# RS485_Communication_Layer.net
KiCad netlist of a schematic drawn in Altium Designer
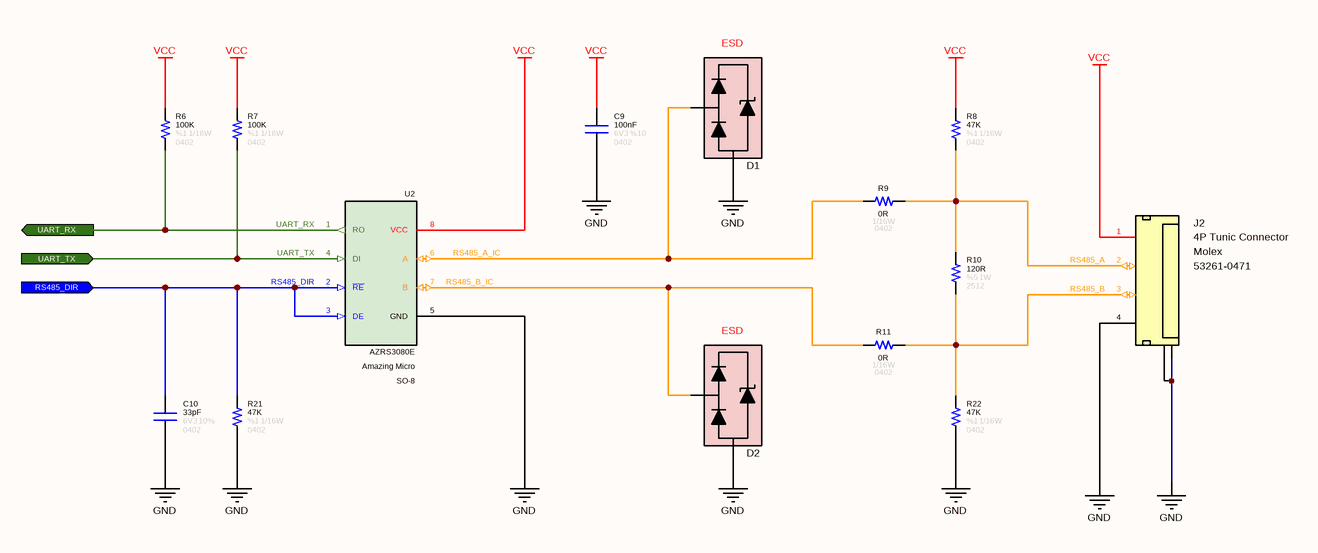
[diagram p0: RS485 Communication Layer.SchDoc]

(export (version "E")
  (design (tool "Eeschema 10.0.6"))
  (components
    (comp (ref "C9")
      (value "100nF")
      (footprint "CAPACITOR_0402")
      (description "Capacitor - 100nF [0402-6V3] (Ceramic)")
      (fields
        (field (name "MANUFACTURER PART NUMBER") "04026D104KAT4A")
        (field (name "TOLERANCE") "%10")
        (field (name "VOLTAGE") "6V3")
        (field (name "CASE") "0402")
        (field (name "Comment") "Capacitor - 100nF [0402] (Ceramic)")
      )
      (libsource (lib "P101DA_Library") (part "Capacitor - 100nF [0402-6V3]"))
    )
    (comp (ref "C10")
      (value "33pF")
      (footprint "CAPACITOR_0402")
      (description "Capacitor - 33pF [0402] (Ceramic)")
      (fields
        (field (name "MANUFACTURER PART NUMBER") "C0402C330J9RACAUTO")
        (field (name "TOLERANCE") "10%")
        (field (name "CASE") "0402")
        (field (name "VOLTAGE") "6V3")
      )
      (libsource (lib "P101DA_Library") (part "Capacitor - 33pF [0402-6V3]"))
    )
    (comp (ref "D1")
      (value "0402ESDA-MLP1")
      (footprint "ESD_0402")
      (description "SUPPRESSOR ESD 30VDC 0402 HFREE")
      (libsource (lib "P101DA_Library") (part "Diode - TPD1E05U06DPYR"))
    )
    (comp (ref "D2")
      (value "0402ESDA-MLP1")
      (footprint "ESD_0402")
      (description "SUPPRESSOR ESD 30VDC 0402 HFREE")
      (libsource (lib "P101DA_Library") (part "Diode - TPD1E05U06DPYR"))
    )
    (comp (ref "J2")
      (value "4P SMD Tunic Connector")
      (footprint "Connector_Tunic 4P")
      (description "Mini Tunic Connector with 4P")
      (fields
        (field (name "MANUFACTURER NAME") "Molex")
        (field (name "MANUFACTURER PART NUMBER") "53261-0471")
      )
      (libsource (lib "P101DA_Library") (part "Connector - Mini Tunic 4P (1.25)"))
    )
    (comp (ref "R6")
      (value "100K")
      (footprint "RESISTOR_0402")
      (description "Thick Film Resistors - SMD 1/16 W 100 KOhm 1%")
      (fields
        (field (name "MANUFACTURER PART NUMBER") "CRCW0402100KFKED")
        (field (name "TOLERANCE") "%1")
        (field (name "CASE") "0402")
        (field (name "POWER") "1/16W")
        (field (name "Comment") "100K - 0402 - %1 - 1/16W")
      )
      (libsource (lib "P101DA_Library") (part "Resistor - 100K [0402]"))
    )
    (comp (ref "R7")
      (value "100K")
      (footprint "RESISTOR_0402")
      (description "Thick Film Resistors - SMD 1/16 W 100 KOhm 1%")
      (fields
        (field (name "MANUFACTURER PART NUMBER") "CRCW0402100KFKED")
        (field (name "TOLERANCE") "%1")
        (field (name "CASE") "0402")
        (field (name "POWER") "1/16W")
        (field (name "Comment") "100K - 0402 - %1 - 1/16W")
      )
      (libsource (lib "P101DA_Library") (part "Resistor - 100K [0402]"))
    )
    (comp (ref "R8")
      (value "47K")
      (footprint "RESISTOR_0402")
      (description "Thick Film Resistors - SMD 1/16 W 47 KOhm 1%")
      (fields
        (field (name "MANUFACTURER PART NUMBER") "CRCW040247K0FKED")
        (field (name "TOLERANCE") "%1")
        (field (name "CASE") "0402")
        (field (name "POWER") "1/16W")
        (field (name "Comment") "47K - 0402 - %1 - 1/16W")
      )
      (libsource (lib "P101DA_Library") (part "Resistor - 47K [0402]"))
    )
    (comp (ref "R9")
      (value "0R")
      (footprint "RESISTOR_0402")
      (description "Thick Film Resistors - SMD 1/16 W 0 Ohm")
      (fields
        (field (name "MANUFACTURER PART NUMBER") "CRCW04020000Z0ED")
        (field (name "CASE") "0402")
        (field (name "POWER") "1/16W")
        (field (name "Comment") "0R - 0402 - %1 - 1/16W")
      )
      (libsource (lib "P101DA_Library") (part "Resistor - 0R [0402]"))
    )
    (comp (ref "R10")
      (value "120R")
      (footprint "RESISTOR_2512")
      (description "Thick Film Resistors - SMD 1 W 120 Ohm 5%")
      (fields
        (field (name "MANUFACTURER PART NUMBER") "RC2512JK-07120RL")
        (field (name "TOLERANCE") "%5")
        (field (name "CASE") "2512")
        (field (name "POWER") "1W")
        (field (name "Comment") "120R - 2512 - %5 - 1W")
      )
      (libsource (lib "P101DA_Library") (part "Resistor - 120R [2512]"))
    )
    (comp (ref "R11")
      (value "0R")
      (footprint "RESISTOR_0402")
      (description "Thick Film Resistors - SMD 1/16 W 0 Ohm")
      (fields
        (field (name "MANUFACTURER PART NUMBER") "CRCW04020000Z0ED")
        (field (name "CASE") "0402")
        (field (name "POWER") "1/16W")
        (field (name "Comment") "0R - 0402 - %1 - 1/16W")
      )
      (libsource (lib "P101DA_Library") (part "Resistor - 0R [0402]"))
    )
    (comp (ref "R21")
      (value "47K")
      (footprint "RESISTOR_0402")
      (description "Thick Film Resistors - SMD 1/16 W 47 KOhm 1%")
      (fields
        (field (name "MANUFACTURER PART NUMBER") "CRCW040247K0FKED")
        (field (name "TOLERANCE") "%1")
        (field (name "CASE") "0402")
        (field (name "POWER") "1/16W")
        (field (name "Comment") "47K - 0402 - %1 - 1/16W")
      )
      (libsource (lib "P101DA_Library") (part "Resistor - 47K [0402]"))
    )
    (comp (ref "R22")
      (value "47K")
      (footprint "RESISTOR_0402")
      (description "Thick Film Resistors - SMD 1/16 W 47 KOhm 1%")
      (fields
        (field (name "MANUFACTURER PART NUMBER") "CRCW040247K0FKED")
        (field (name "TOLERANCE") "%1")
        (field (name "CASE") "0402")
        (field (name "POWER") "1/16W")
        (field (name "Comment") "47K - 0402 - %1 - 1/16W")
      )
      (libsource (lib "P101DA_Library") (part "Resistor - 47K [0402]"))
    )
    (comp (ref "U2")
      (value "RS485 Modulator")
      (footprint "SOP-8L (AZRS3080E)")
      (description "Half-duplex RS485 transceiver.")
      (fields
        (field (name "CASE") "SO-8")
        (field (name "MANUFACTURER PART NUMBER") "AZRS3080E")
        (field (name "MANUFACTURER NAME") "Amazing Micro")
      )
      (libsource (lib "P101DA_Library") (part "IC - AZRS3080E"))
    )
  )
  (nets
    (net (code "1") (name "/RS485_A") (class "Default")
      (node (ref "J2") (pin "2") (pinfunction "Pin-2_2") (pintype "bidirectional"))
      (node (ref "R10") (pin "2") (pinfunction "2_2") (pintype "passive"))
      (node (ref "R8") (pin "1") (pinfunction "1_1") (pintype "passive"))
      (node (ref "R9") (pin "1") (pinfunction "1_1") (pintype "passive"))
    )
    (net (code "2") (name "/RS485_A_IC") (class "Default")
      (node (ref "D1") (pin "1") (pinfunction "I/O_1") (pintype "passive"))
      (node (ref "R9") (pin "2") (pinfunction "2_2") (pintype "passive"))
      (node (ref "U2") (pin "6") (pinfunction "A_6") (pintype "bidirectional"))
    )
    (net (code "3") (name "/RS485_B") (class "Default")
      (node (ref "J2") (pin "3") (pinfunction "Pin-3_3") (pintype "bidirectional"))
      (node (ref "R10") (pin "1") (pinfunction "1_1") (pintype "passive"))
      (node (ref "R11") (pin "1") (pinfunction "1_1") (pintype "passive"))
      (node (ref "R22") (pin "2") (pinfunction "2_2") (pintype "passive"))
    )
    (net (code "4") (name "/RS485_B_IC") (class "Default")
      (node (ref "D2") (pin "1") (pinfunction "I/O_1") (pintype "passive"))
      (node (ref "R11") (pin "2") (pinfunction "2_2") (pintype "passive"))
      (node (ref "U2") (pin "7") (pinfunction "B_7") (pintype "bidirectional"))
    )
    (net (code "5") (name "/RS485_DIR") (class "Default")
      (node (ref "C10") (pin "2") (pinfunction "2_2") (pintype "passive"))
      (node (ref "R21") (pin "2") (pinfunction "2_2") (pintype "passive"))
      (node (ref "U2") (pin "2") (pinfunction "~{RE}_2") (pintype "input"))
      (node (ref "U2") (pin "3") (pinfunction "DE_3") (pintype "input"))
    )
    (net (code "6") (name "/UART_RX") (class "Default")
      (node (ref "R6") (pin "1") (pinfunction "1_1") (pintype "passive"))
      (node (ref "U2") (pin "1") (pinfunction "RO_1") (pintype "output"))
    )
    (net (code "7") (name "/UART_TX") (class "Default")
      (node (ref "R7") (pin "1") (pinfunction "1_1") (pintype "passive"))
      (node (ref "U2") (pin "4") (pinfunction "DI_4") (pintype "input"))
    )
    (net (code "8") (name "GND") (class "Default")
      (node (ref "C10") (pin "1") (pinfunction "1_1") (pintype "passive"))
      (node (ref "C9") (pin "1") (pinfunction "1_1") (pintype "passive"))
      (node (ref "D1") (pin "2") (pinfunction "GND_2") (pintype "passive"))
      (node (ref "D2") (pin "2") (pinfunction "GND_2") (pintype "passive"))
      (node (ref "J2") (pin "4") (pinfunction "Pin-4_4") (pintype "power_in"))
      (node (ref "J2") (pin "5") (pinfunction "GND_5") (pintype "passive"))
      (node (ref "J2") (pin "6") (pinfunction "GND_6") (pintype "passive"))
      (node (ref "R21") (pin "1") (pinfunction "1_1") (pintype "passive"))
      (node (ref "R22") (pin "1") (pinfunction "1_1") (pintype "passive"))
      (node (ref "U2") (pin "5") (pinfunction "GND_5") (pintype "passive"))
    )
    (net (code "9") (name "VCC") (class "Default")
      (node (ref "C9") (pin "2") (pinfunction "2_2") (pintype "passive"))
      (node (ref "J2") (pin "1") (pinfunction "Pin-1_1") (pintype "power_in"))
      (node (ref "R6") (pin "2") (pinfunction "2_2") (pintype "passive"))
      (node (ref "R7") (pin "2") (pinfunction "2_2") (pintype "passive"))
      (node (ref "R8") (pin "2") (pinfunction "2_2") (pintype "passive"))
      (node (ref "U2") (pin "8") (pinfunction "VCC_8") (pintype "power_in"))
    )
  )
)
